# load_cell_amp.net
KiCad netlist of a schematic drawn in EAGLE
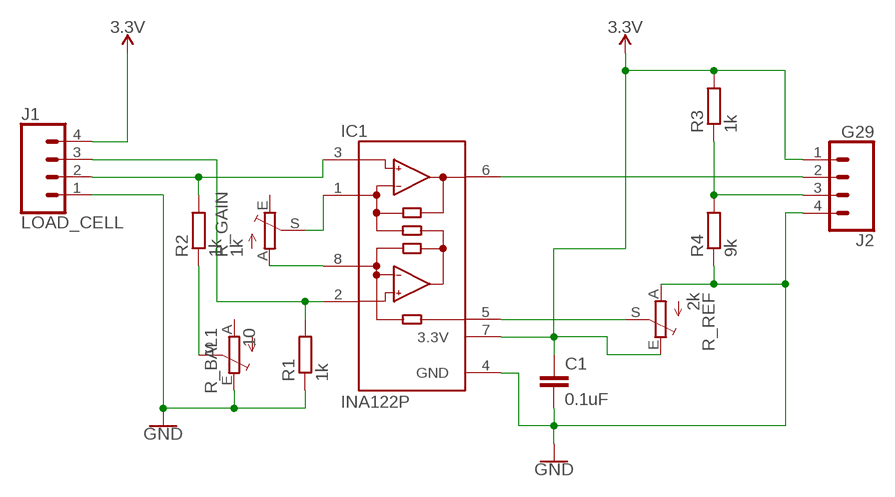
[diagram p0: schematic, sheet 1]

(export (version "E")
  (design (tool "Eeschema 10.0.6"))
  (components
    (comp (ref "C1")
      (value "0.1uF")
      (footprint "eagle-import:C025-024X044")
      (libsource (lib "eagle-import") (part "C-EU025-024X044"))
    )
    (comp (ref "IC1")
      (value "INA122P")
      (footprint "eagle-import:DIL08")
      (fields (field (name "MF") "TEXAS INSTRUMENTS"))
      (libsource (lib "eagle-import") (part "INA122P"))
    )
    (comp (ref "J1")
      (value "LOAD_CELL")
      (footprint "eagle-import:04P")
      (libsource (lib "eagle-import") (part "M04"))
    )
    (comp (ref "J2")
      (value "G29")
      (footprint "eagle-import:04P")
      (libsource (lib "eagle-import") (part "M04"))
    )
    (comp (ref "R1")
      (value "1k")
      (footprint "eagle-import:0207_10")
      (libsource (lib "eagle-import") (part "R-EU_0207/10"))
    )
    (comp (ref "R2")
      (value "1k")
      (footprint "eagle-import:0207_10")
      (libsource (lib "eagle-import") (part "R-EU_0207/10"))
    )
    (comp (ref "R3")
      (value "1k")
      (footprint "eagle-import:0207_10")
      (libsource (lib "eagle-import") (part "R-EU_0207/10"))
    )
    (comp (ref "R4")
      (value "9k")
      (footprint "eagle-import:0207_10")
      (libsource (lib "eagle-import") (part "R-EU_0207/10"))
    )
    (comp (ref "R_BAL1")
      (value "10")
      (footprint "eagle-import:RJ9W")
      (libsource (lib "eagle-import") (part "TRIM_EU-RJ9W"))
    )
    (comp (ref "R_GAIN")
      (value "1k")
      (footprint "eagle-import:RJ9W")
      (libsource (lib "eagle-import") (part "TRIM_EU-RJ9W"))
    )
    (comp (ref "R_REF")
      (value "2k")
      (footprint "eagle-import:RJ9W")
      (libsource (lib "eagle-import") (part "TRIM_EU-RJ9W"))
    )
  )
  (nets
    (net (code "1") (name "3.3V") (class "Default")
      (node (ref "C1") (pin "1") (pinfunction "1_1") (pintype "passive"))
      (node (ref "IC1") (pin "7") (pinfunction "3.3V_7") (pintype "power_in"))
      (node (ref "J1") (pin "4") (pinfunction "4_4") (pintype "passive"))
      (node (ref "J2") (pin "1") (pinfunction "1_1") (pintype "passive"))
      (node (ref "R3") (pin "2") (pinfunction "2_2") (pintype "passive"))
      (node (ref "R_REF") (pin "E") (pinfunction "E_E") (pintype "passive"))
    )
    (net (code "2") (name "GND") (class "Default")
      (node (ref "C1") (pin "2") (pinfunction "2_2") (pintype "passive"))
      (node (ref "IC1") (pin "4") (pinfunction "GND_4") (pintype "power_in"))
      (node (ref "J1") (pin "1") (pinfunction "1_1") (pintype "passive"))
      (node (ref "J2") (pin "4") (pinfunction "4_4") (pintype "passive"))
      (node (ref "R1") (pin "1") (pinfunction "1_1") (pintype "passive"))
      (node (ref "R4") (pin "1") (pinfunction "1_1") (pintype "passive"))
      (node (ref "R_BAL1") (pin "E") (pinfunction "E_E") (pintype "passive"))
      (node (ref "R_REF") (pin "A") (pinfunction "A_A") (pintype "passive"))
    )
    (net (code "3") (name "Net-(IC1-+IN)") (class "Default")
      (node (ref "IC1") (pin "3") (pinfunction "+IN_3") (pintype "input"))
      (node (ref "J1") (pin "2") (pinfunction "2_2") (pintype "passive"))
      (node (ref "R2") (pin "2") (pinfunction "2_2") (pintype "passive"))
    )
    (net (code "4") (name "Net-(IC1--IN)") (class "Default")
      (node (ref "IC1") (pin "2") (pinfunction "-IN_2") (pintype "input"))
      (node (ref "J1") (pin "3") (pinfunction "3_3") (pintype "passive"))
      (node (ref "R1") (pin "2") (pinfunction "2_2") (pintype "passive"))
    )
    (net (code "5") (name "Net-(IC1-OUT)") (class "Default")
      (node (ref "IC1") (pin "6") (pinfunction "OUT_6") (pintype "output"))
      (node (ref "J2") (pin "2") (pinfunction "2_2") (pintype "passive"))
    )
    (net (code "6") (name "Net-(IC1-REF)") (class "Default")
      (node (ref "IC1") (pin "5") (pinfunction "REF_5") (pintype "passive"))
      (node (ref "R_REF") (pin "S") (pinfunction "S_S") (pintype "passive"))
    )
    (net (code "7") (name "Net-(IC1-RG-Pad1)") (class "Default")
      (node (ref "IC1") (pin "1") (pinfunction "RG_1") (pintype "passive"))
      (node (ref "R_GAIN") (pin "S") (pinfunction "S_S") (pintype "passive"))
    )
    (net (code "8") (name "Net-(IC1-RG-Pad8)") (class "Default")
      (node (ref "IC1") (pin "8") (pinfunction "RG_8") (pintype "passive"))
      (node (ref "R_GAIN") (pin "A") (pinfunction "A_A") (pintype "passive"))
    )
    (net (code "9") (name "Net-(J2-Pad3)") (class "Default")
      (node (ref "J2") (pin "3") (pinfunction "3_3") (pintype "passive"))
      (node (ref "R3") (pin "1") (pinfunction "1_1") (pintype "passive"))
      (node (ref "R4") (pin "2") (pinfunction "2_2") (pintype "passive"))
    )
    (net (code "10") (name "Net-(R2-Pad1)") (class "Default")
      (node (ref "R2") (pin "1") (pinfunction "1_1") (pintype "passive"))
      (node (ref "R_BAL1") (pin "S") (pinfunction "S_S") (pintype "passive"))
    )
    (net (code "11") (name "unconnected-(R_BAL1-PadA)") (class "Default")
      (node (ref "R_BAL1") (pin "A") (pinfunction "A_A") (pintype "passive"))
    )
    (net (code "12") (name "unconnected-(R_GAIN-PadE)") (class "Default")
      (node (ref "R_GAIN") (pin "E") (pinfunction "E_E") (pintype "passive"))
    )
  )
)
